# esp32s3_del_v1.net
KiCad netlist of a schematic drawn in EasyEDA Pro
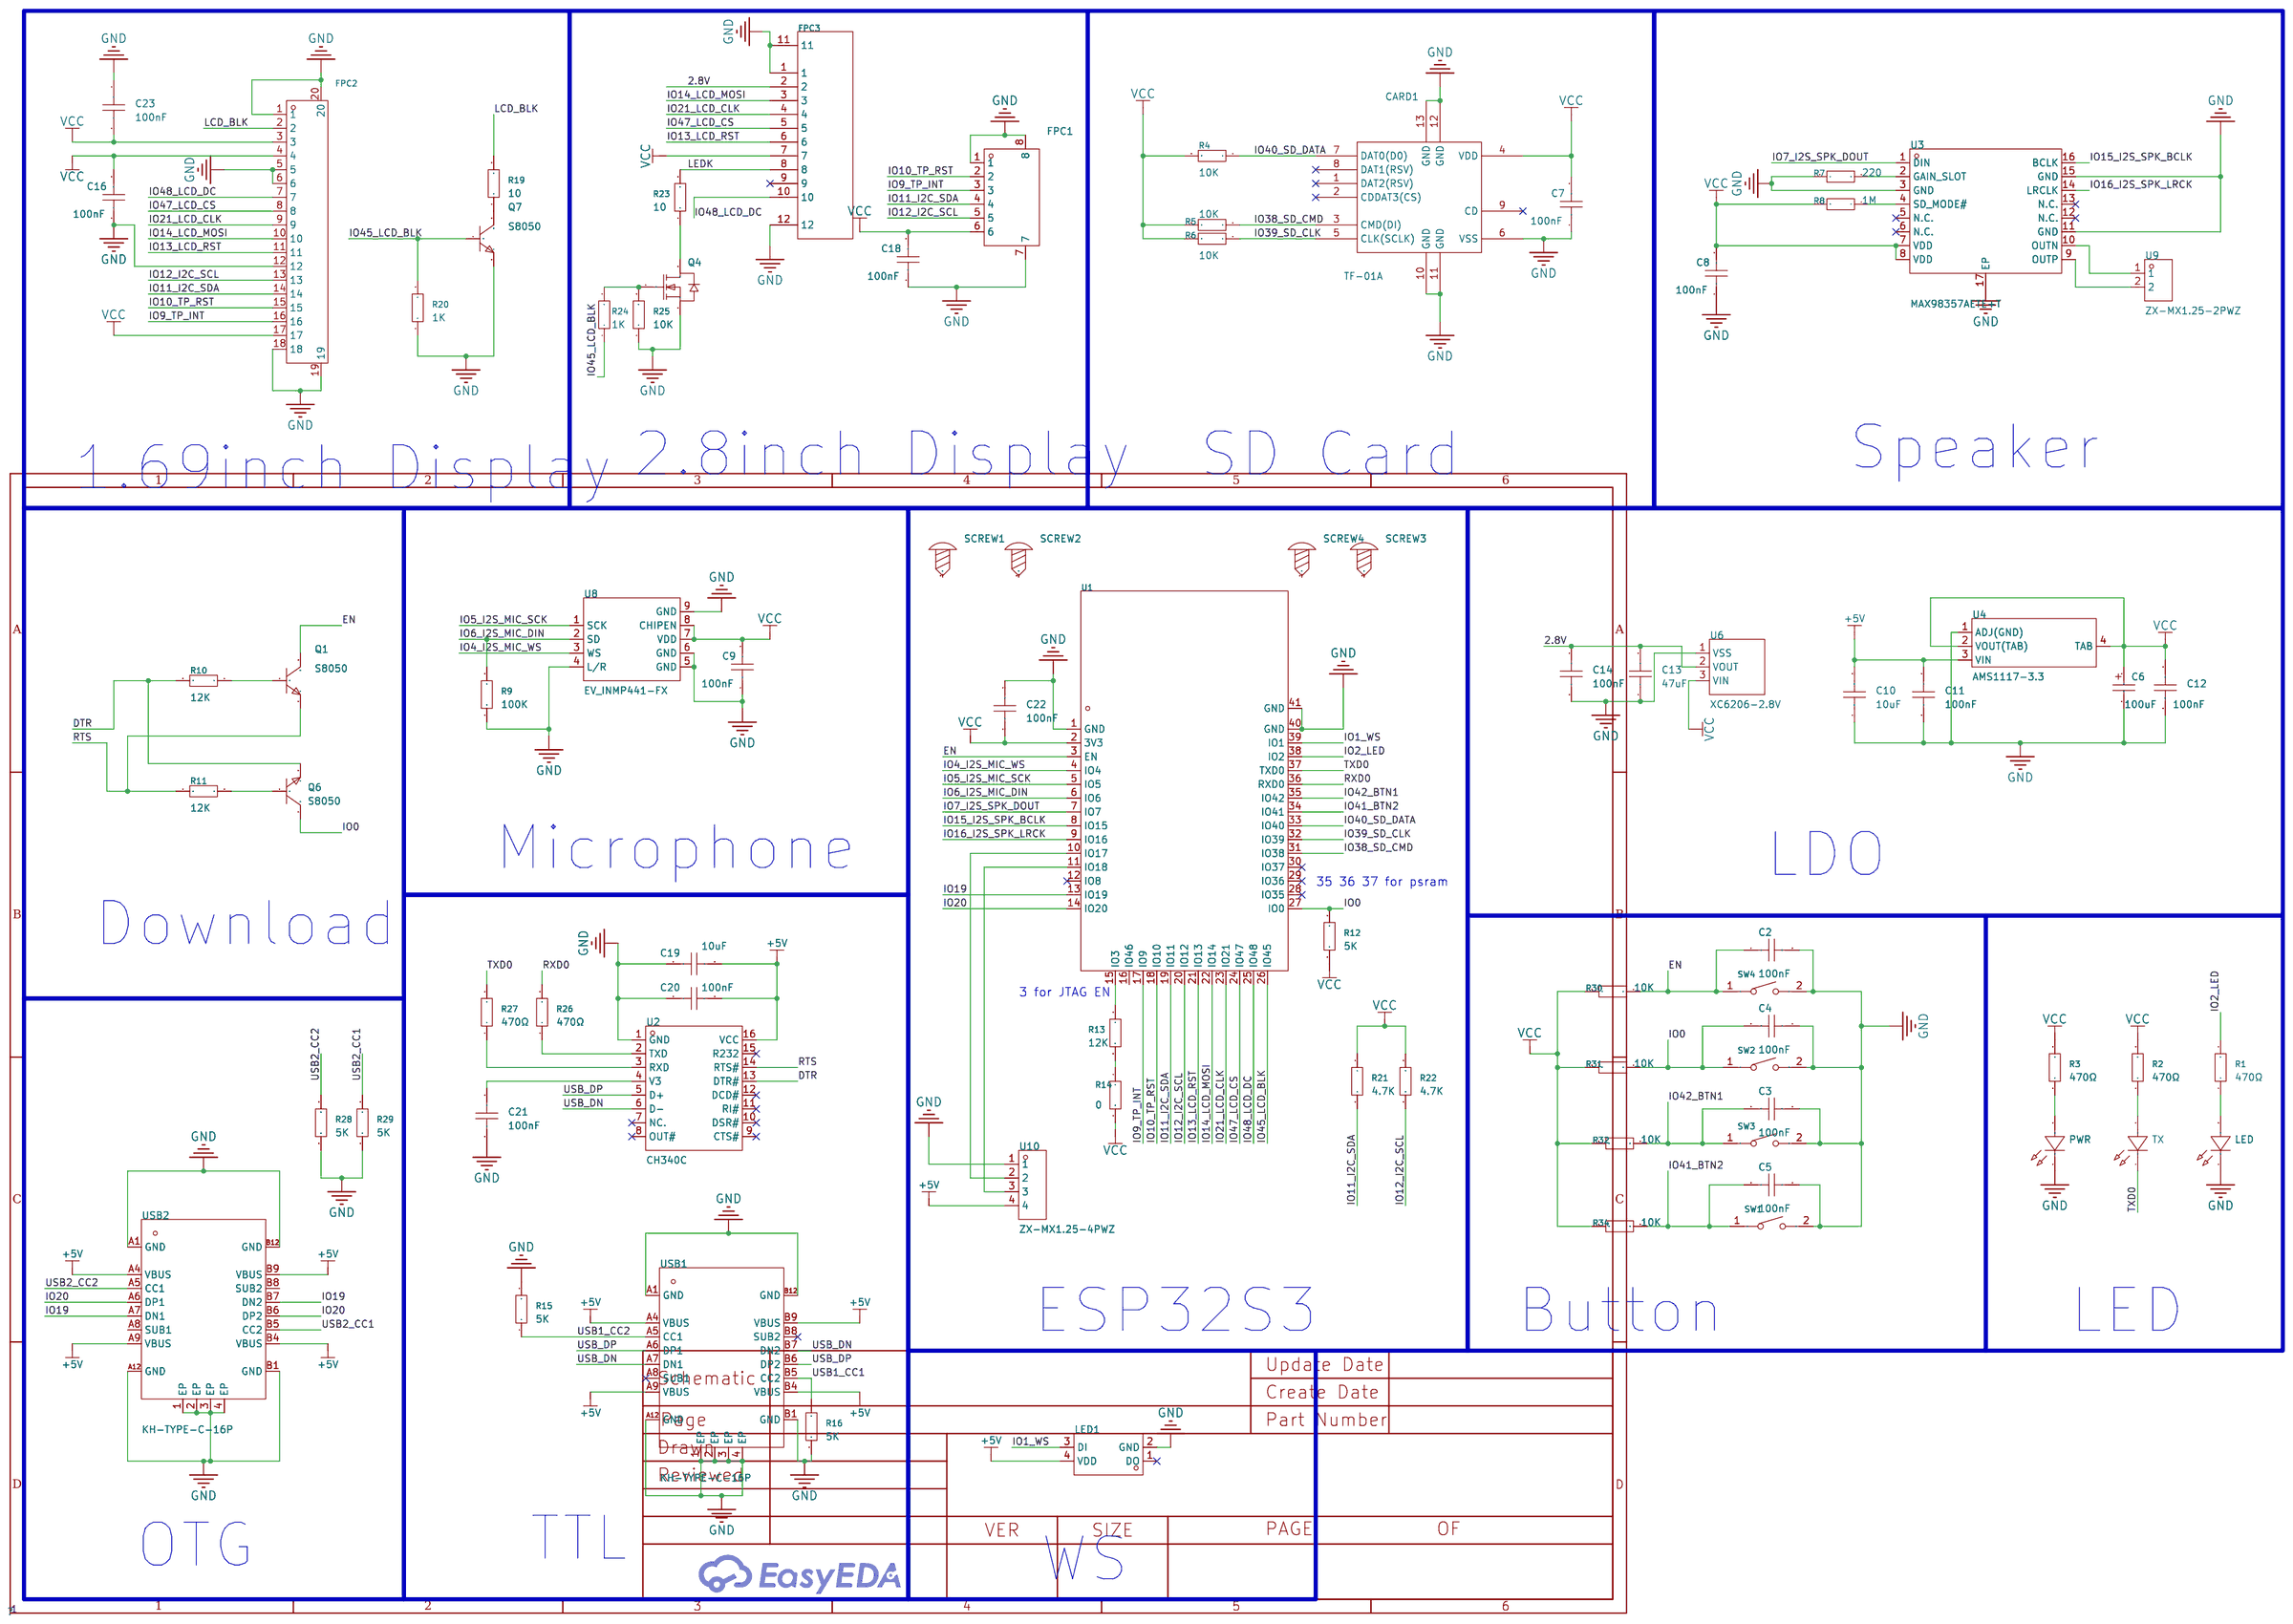
[diagram p0: schematic sheet]

(export (version "E")
  (design (tool "Eeschema 10.0.6"))
  (components
    (comp (ref "C2")
      (value "100nF")
      (footprint "easyedapro:C0402")
      (fields
        (field (name "Manufacturer Part") "CL05B104KO5NNNC")
        (field (name "Manufacturer") "SAMSUNG(三星)")
      )
      (libsource (lib "easyedapro") (part "CL05B104KO5NNNC"))
    )
    (comp (ref "C3")
      (value "100nF")
      (footprint "easyedapro:C0402")
      (fields
        (field (name "Manufacturer Part") "CL05B104KO5NNNC")
        (field (name "Manufacturer") "SAMSUNG(三星)")
      )
      (libsource (lib "easyedapro") (part "CL05B104KO5NNNC"))
    )
    (comp (ref "C4")
      (value "100nF")
      (footprint "easyedapro:C0402")
      (fields
        (field (name "Manufacturer Part") "CL05B104KO5NNNC")
        (field (name "Manufacturer") "SAMSUNG(三星)")
      )
      (libsource (lib "easyedapro") (part "CL05B104KO5NNNC"))
    )
    (comp (ref "C5")
      (value "100nF")
      (footprint "easyedapro:C0402")
      (fields
        (field (name "Manufacturer Part") "CL05B104KO5NNNC")
        (field (name "Manufacturer") "SAMSUNG(三星)")
      )
      (libsource (lib "easyedapro") (part "CL05B104KO5NNNC"))
    )
    (comp (ref "C6")
      (value "100uF")
      (footprint "easyedapro:CASE-B_3528")
      (fields (field (name "Manufacturer Part") "TAJB107K006RNJ") (field (name "Manufacturer") "Kyocera AVX"))
      (libsource (lib "easyedapro") (part "TAJB107K006RNJ"))
    )
    (comp (ref "C7")
      (value "100nF")
      (footprint "easyedapro:C0402")
      (fields
        (field (name "Manufacturer Part") "CL05B104KO5NNNC")
        (field (name "Manufacturer") "SAMSUNG(三星)")
      )
      (libsource (lib "easyedapro") (part "CL05B104KO5NNNC"))
    )
    (comp (ref "C8")
      (value "100nF")
      (footprint "easyedapro:C0402")
      (fields
        (field (name "Manufacturer Part") "CL05B104KO5NNNC")
        (field (name "Manufacturer") "SAMSUNG(三星)")
      )
      (libsource (lib "easyedapro") (part "CL05B104KO5NNNC"))
    )
    (comp (ref "C9")
      (value "100nF")
      (footprint "easyedapro:C0402")
      (fields
        (field (name "Manufacturer Part") "CL05B104KO5NNNC")
        (field (name "Manufacturer") "SAMSUNG(三星)")
      )
      (libsource (lib "easyedapro") (part "CL05B104KO5NNNC"))
    )
    (comp (ref "C10")
      (value "10uF")
      (footprint "easyedapro:C0603")
      (description "Capacitance:10uF Tolerance:±10% Tolerance:±10% Voltage Rating:10V Temperature Coefficient:X5R")
      (fields
        (field (name "Manufacturer Part") "CGA0603X5R106K100JT")
        (field (name "Manufacturer") "HRE(芯声)")
      )
      (libsource (lib "easyedapro") (part "CGA0603X5R106K100JT"))
    )
    (comp (ref "C11")
      (value "100nF")
      (footprint "easyedapro:C0402")
      (fields
        (field (name "Manufacturer Part") "CL05B104KO5NNNC")
        (field (name "Manufacturer") "SAMSUNG(三星)")
      )
      (libsource (lib "easyedapro") (part "CL05B104KO5NNNC"))
    )
    (comp (ref "C12")
      (value "100nF")
      (footprint "easyedapro:C0402")
      (fields
        (field (name "Manufacturer Part") "CL05B104KO5NNNC")
        (field (name "Manufacturer") "SAMSUNG(三星)")
      )
      (libsource (lib "easyedapro") (part "CL05B104KO5NNNC"))
    )
    (comp (ref "C13")
      (value "47uF")
      (footprint "easyedapro:C0603")
      (description "Capacitance:10uF Tolerance:±10% Tolerance:±10% Voltage Rating:10V Temperature Coefficient:X5R")
      (fields
        (field (name "Manufacturer Part") "CGA0603X5R106K100JT")
        (field (name "Manufacturer") "HRE(芯声)")
      )
      (libsource (lib "easyedapro") (part "CGA0603X5R106K100JT"))
    )
    (comp (ref "C14")
      (value "100nF")
      (footprint "easyedapro:C0402")
      (fields
        (field (name "Manufacturer Part") "CL05B104KO5NNNC")
        (field (name "Manufacturer") "SAMSUNG(三星)")
      )
      (libsource (lib "easyedapro") (part "CL05B104KO5NNNC"))
    )
    (comp (ref "C16")
      (value "100nF")
      (footprint "easyedapro:C0402")
      (fields
        (field (name "Manufacturer Part") "CL05B104KO5NNNC")
        (field (name "Manufacturer") "SAMSUNG(三星)")
      )
      (libsource (lib "easyedapro") (part "CL05B104KO5NNNC"))
    )
    (comp (ref "C18")
      (value "100nF")
      (footprint "easyedapro:C0402")
      (fields
        (field (name "Manufacturer Part") "CL05B104KO5NNNC")
        (field (name "Manufacturer") "SAMSUNG(三星)")
      )
      (libsource (lib "easyedapro") (part "CL05B104KO5NNNC"))
    )
    (comp (ref "C19")
      (value "10uF")
      (footprint "easyedapro:C0603")
      (description "Capacitance:10uF Tolerance:±10% Tolerance:±10% Voltage Rating:10V Temperature Coefficient:X5R")
      (fields
        (field (name "Manufacturer Part") "CGA0603X5R106K100JT")
        (field (name "Manufacturer") "HRE(芯声)")
      )
      (libsource (lib "easyedapro") (part "CGA0603X5R106K100JT"))
    )
    (comp (ref "C20")
      (value "100nF")
      (footprint "easyedapro:C0402")
      (fields
        (field (name "Manufacturer Part") "CL05B104KO5NNNC")
        (field (name "Manufacturer") "SAMSUNG(三星)")
      )
      (libsource (lib "easyedapro") (part "CL05B104KO5NNNC"))
    )
    (comp (ref "C21")
      (value "100nF")
      (footprint "easyedapro:C0402")
      (fields
        (field (name "Manufacturer Part") "CL05B104KO5NNNC")
        (field (name "Manufacturer") "SAMSUNG(三星)")
      )
      (libsource (lib "easyedapro") (part "CL05B104KO5NNNC"))
    )
    (comp (ref "C22")
      (value "100nF")
      (footprint "easyedapro:C0402")
      (fields
        (field (name "Manufacturer Part") "CL05B104KO5NNNC")
        (field (name "Manufacturer") "SAMSUNG(三星)")
      )
      (libsource (lib "easyedapro") (part "CL05B104KO5NNNC"))
    )
    (comp (ref "C23")
      (value "100nF")
      (footprint "easyedapro:C0402")
      (fields
        (field (name "Manufacturer Part") "CL05B104KO5NNNC")
        (field (name "Manufacturer") "SAMSUNG(三星)")
      )
      (libsource (lib "easyedapro") (part "CL05B104KO5NNNC"))
    )
    (comp (ref "CARD1")
      (value "TF-01A")
      (footprint "easyedapro:TF-SMD_TF-01A")
      (fields (field (name "Manufacturer") "韩国韩荣"))
      (libsource (lib "easyedapro") (part "TF-01A"))
    )
    (comp (ref "FPC1")
      (value "0.5K-DX-6PWBG")
      (footprint "easyedapro:FPC-SMD_6P-P0.50_DEALON_0.5K-DX-6PWB")
      (fields (field (name "Manufacturer") "HDGC(华德共创)"))
      (libsource (lib "easyedapro") (part "0.5K-DX-6PWBG"))
    )
    (comp (ref "FPC2")
      (value "FPC-05F-18PH20")
      (footprint "easyedapro:FPC-SMD_18P-P0.50_FPC-05F-18PH20")
      (fields (field (name "Manufacturer") "XUNPU(讯普)"))
      (libsource (lib "easyedapro") (part "FPC-05F-18PH20"))
    )
    (comp (ref "FPC3")
      (value "AFC07-S10ECA-00")
      (footprint "easyedapro:FPC-SMD_P0.50-10P_LCS-SJ-H2.0")
      (fields (field (name "Manufacturer") "JS(钜硕电子)"))
      (libsource (lib "easyedapro") (part "AFC07-S10ECA-00"))
    )
    (comp (ref "LED")
      (value "XL-1608SURC-06")
      (footprint "easyedapro:LED0603-RD_RED")
      (fields (field (name "Manufacturer") "XINGLIGHT(成兴光)"))
      (libsource (lib "easyedapro") (part "XL-1608SURC-06"))
    )
    (comp (ref "LED1")
      (value "XL-2020RGBC-WS2812B")
      (footprint "easyedapro:LED-SMD_4P-L2.0-W2.0-BR-1")
      (fields (field (name "Manufacturer") "XINGLIGHT(成兴光)"))
      (libsource (lib "easyedapro") (part "XL-2020RGBC-WS2812B"))
    )
    (comp (ref "PWR")
      (value "XL-1608SURC-06")
      (footprint "easyedapro:LED0603-RD_RED")
      (fields (field (name "Manufacturer") "XINGLIGHT(成兴光)"))
      (libsource (lib "easyedapro") (part "XL-1608SURC-06"))
    )
    (comp (ref "Q1")
      (value "S8050")
      (footprint "easyedapro:SOT-23-3_L2.9-W1.3-P1.90-LS2.3-BR")
      (fields (field (name "Manufacturer") "宏嘉诚"))
      (libsource (lib "easyedapro") (part "S8050_C20069125"))
    )
    (comp (ref "Q4")
      (value "Si2302CDS-T1-GE3")
      (footprint "easyedapro:SOT-23_L2.9-W1.3-P1.90-LS2.4-BR")
      (fields (field (name "Manufacturer") "VISHAY(威世)"))
      (libsource (lib "easyedapro") (part "Si2302CDS-T1-GE3"))
    )
    (comp (ref "Q6")
      (value "S8050")
      (footprint "easyedapro:SOT-23-3_L2.9-W1.3-P1.90-LS2.3-BR")
      (fields (field (name "Manufacturer") "宏嘉诚"))
      (libsource (lib "easyedapro") (part "S8050_C20069125"))
    )
    (comp (ref "Q7")
      (value "S8050")
      (footprint "easyedapro:SOT-23-3_L2.9-W1.3-P1.90-LS2.3-BR")
      (fields (field (name "Manufacturer") "宏嘉诚"))
      (libsource (lib "easyedapro") (part "S8050_C20069125"))
    )
    (comp (ref "R1")
      (value "470Ω")
      (footprint "easyedapro:R0402")
      (fields
        (field (name "Manufacturer Part") "0402WGF4700TCE")
        (field (name "Manufacturer") "UNI-ROYAL(厚声)")
      )
      (libsource (lib "easyedapro") (part "0402WGF4700TCE"))
    )
    (comp (ref "R2")
      (value "470Ω")
      (footprint "easyedapro:R0402")
      (fields
        (field (name "Manufacturer Part") "0402WGF4700TCE")
        (field (name "Manufacturer") "UNI-ROYAL(厚声)")
      )
      (libsource (lib "easyedapro") (part "0402WGF4700TCE"))
    )
    (comp (ref "R3")
      (value "470Ω")
      (footprint "easyedapro:R0402")
      (fields
        (field (name "Manufacturer Part") "0402WGF4700TCE")
        (field (name "Manufacturer") "UNI-ROYAL(厚声)")
      )
      (libsource (lib "easyedapro") (part "0402WGF4700TCE"))
    )
    (comp (ref "R4")
      (value "10K")
      (footprint "easyedapro:R0402")
      (fields
        (field (name "Manufacturer Part") "0402WGF4700TCE")
        (field (name "Manufacturer") "UNI-ROYAL(厚声)")
      )
      (libsource (lib "easyedapro") (part "0402WGF4700TCE"))
    )
    (comp (ref "R5")
      (value "10K")
      (footprint "easyedapro:R0402")
      (fields
        (field (name "Manufacturer Part") "0402WGF4700TCE")
        (field (name "Manufacturer") "UNI-ROYAL(厚声)")
      )
      (libsource (lib "easyedapro") (part "0402WGF4700TCE"))
    )
    (comp (ref "R6")
      (value "10K")
      (footprint "easyedapro:R0402")
      (fields
        (field (name "Manufacturer Part") "0402WGF4700TCE")
        (field (name "Manufacturer") "UNI-ROYAL(厚声)")
      )
      (libsource (lib "easyedapro") (part "0402WGF4700TCE"))
    )
    (comp (ref "R7")
      (value "220")
      (footprint "easyedapro:R0402")
      (fields
        (field (name "Manufacturer Part") "0402WGF4700TCE")
        (field (name "Manufacturer") "UNI-ROYAL(厚声)")
      )
      (libsource (lib "easyedapro") (part "0402WGF4700TCE"))
    )
    (comp (ref "R8")
      (value "1M")
      (footprint "easyedapro:R0402")
      (fields
        (field (name "Manufacturer Part") "0402WGF4700TCE")
        (field (name "Manufacturer") "UNI-ROYAL(厚声)")
      )
      (libsource (lib "easyedapro") (part "0402WGF4700TCE"))
    )
    (comp (ref "R9")
      (value "100K")
      (footprint "easyedapro:R0402")
      (fields
        (field (name "Manufacturer Part") "0402WGF4700TCE")
        (field (name "Manufacturer") "UNI-ROYAL(厚声)")
      )
      (libsource (lib "easyedapro") (part "0402WGF4700TCE"))
    )
    (comp (ref "R10")
      (value "12K")
      (footprint "easyedapro:R0402")
      (fields
        (field (name "Manufacturer Part") "0402WGF4700TCE")
        (field (name "Manufacturer") "UNI-ROYAL(厚声)")
      )
      (libsource (lib "easyedapro") (part "0402WGF4700TCE"))
    )
    (comp (ref "R11")
      (value "12K")
      (footprint "easyedapro:R0402")
      (fields
        (field (name "Manufacturer Part") "0402WGF4700TCE")
        (field (name "Manufacturer") "UNI-ROYAL(厚声)")
      )
      (libsource (lib "easyedapro") (part "0402WGF4700TCE"))
    )
    (comp (ref "R12")
      (value "5K")
      (footprint "easyedapro:R0402")
      (fields
        (field (name "Manufacturer Part") "0402WGF4700TCE")
        (field (name "Manufacturer") "UNI-ROYAL(厚声)")
      )
      (libsource (lib "easyedapro") (part "0402WGF4700TCE"))
    )
    (comp (ref "R13")
      (value "12K")
      (footprint "easyedapro:R0402")
      (fields
        (field (name "Manufacturer Part") "0402WGF4700TCE")
        (field (name "Manufacturer") "UNI-ROYAL(厚声)")
      )
      (libsource (lib "easyedapro") (part "0402WGF4700TCE"))
    )
    (comp (ref "R14")
      (value "0")
      (footprint "easyedapro:R0402")
      (fields
        (field (name "Manufacturer Part") "0402WGF4700TCE")
        (field (name "Manufacturer") "UNI-ROYAL(厚声)")
      )
      (libsource (lib "easyedapro") (part "0402WGF4700TCE"))
    )
    (comp (ref "R15")
      (value "5K")
      (footprint "easyedapro:R0402")
      (fields
        (field (name "Manufacturer Part") "0402WGF4700TCE")
        (field (name "Manufacturer") "UNI-ROYAL(厚声)")
      )
      (libsource (lib "easyedapro") (part "0402WGF4700TCE"))
    )
    (comp (ref "R16")
      (value "5K")
      (footprint "easyedapro:R0402")
      (fields
        (field (name "Manufacturer Part") "0402WGF4700TCE")
        (field (name "Manufacturer") "UNI-ROYAL(厚声)")
      )
      (libsource (lib "easyedapro") (part "0402WGF4700TCE"))
    )
    (comp (ref "R19")
      (value "10")
      (footprint "easyedapro:R0402")
      (fields
        (field (name "Manufacturer Part") "0402WGF4700TCE")
        (field (name "Manufacturer") "UNI-ROYAL(厚声)")
      )
      (libsource (lib "easyedapro") (part "0402WGF4700TCE"))
    )
    (comp (ref "R20")
      (value "1K")
      (footprint "easyedapro:R0402")
      (fields
        (field (name "Manufacturer Part") "0402WGF4700TCE")
        (field (name "Manufacturer") "UNI-ROYAL(厚声)")
      )
      (libsource (lib "easyedapro") (part "0402WGF4700TCE"))
    )
    (comp (ref "R21")
      (value "4.7K")
      (footprint "easyedapro:R0402")
      (fields
        (field (name "Manufacturer Part") "0402WGF4700TCE")
        (field (name "Manufacturer") "UNI-ROYAL(厚声)")
      )
      (libsource (lib "easyedapro") (part "0402WGF4700TCE"))
    )
    (comp (ref "R22")
      (value "4.7K")
      (footprint "easyedapro:R0402")
      (fields
        (field (name "Manufacturer Part") "0402WGF4700TCE")
        (field (name "Manufacturer") "UNI-ROYAL(厚声)")
      )
      (libsource (lib "easyedapro") (part "0402WGF4700TCE"))
    )
    (comp (ref "R23")
      (value "10")
      (footprint "easyedapro:R0402")
      (fields
        (field (name "Manufacturer Part") "0402WGF4700TCE")
        (field (name "Manufacturer") "UNI-ROYAL(厚声)")
      )
      (libsource (lib "easyedapro") (part "0402WGF4700TCE"))
    )
    (comp (ref "R24")
      (value "1K")
      (footprint "easyedapro:R0402")
      (fields
        (field (name "Manufacturer Part") "0402WGF4700TCE")
        (field (name "Manufacturer") "UNI-ROYAL(厚声)")
      )
      (libsource (lib "easyedapro") (part "0402WGF4700TCE"))
    )
    (comp (ref "R25")
      (value "10K")
      (footprint "easyedapro:R0402")
      (fields
        (field (name "Manufacturer Part") "0402WGF4700TCE")
        (field (name "Manufacturer") "UNI-ROYAL(厚声)")
      )
      (libsource (lib "easyedapro") (part "0402WGF4700TCE"))
    )
    (comp (ref "R26")
      (value "470Ω")
      (footprint "easyedapro:R0402")
      (fields
        (field (name "Manufacturer Part") "0402WGF4700TCE")
        (field (name "Manufacturer") "UNI-ROYAL(厚声)")
      )
      (libsource (lib "easyedapro") (part "0402WGF4700TCE"))
    )
    (comp (ref "R27")
      (value "470Ω")
      (footprint "easyedapro:R0402")
      (fields
        (field (name "Manufacturer Part") "0402WGF4700TCE")
        (field (name "Manufacturer") "UNI-ROYAL(厚声)")
      )
      (libsource (lib "easyedapro") (part "0402WGF4700TCE"))
    )
    (comp (ref "R28")
      (value "5K")
      (footprint "easyedapro:R0402")
      (fields
        (field (name "Manufacturer Part") "0402WGF4700TCE")
        (field (name "Manufacturer") "UNI-ROYAL(厚声)")
      )
      (libsource (lib "easyedapro") (part "0402WGF4700TCE"))
    )
    (comp (ref "R29")
      (value "5K")
      (footprint "easyedapro:R0402")
      (fields
        (field (name "Manufacturer Part") "0402WGF4700TCE")
        (field (name "Manufacturer") "UNI-ROYAL(厚声)")
      )
      (libsource (lib "easyedapro") (part "0402WGF4700TCE"))
    )
    (comp (ref "R30")
      (value "10K")
      (footprint "easyedapro:R0402")
      (fields
        (field (name "Manufacturer Part") "0402WGF4700TCE")
        (field (name "Manufacturer") "UNI-ROYAL(厚声)")
      )
      (libsource (lib "easyedapro") (part "0402WGF4700TCE"))
    )
    (comp (ref "R31")
      (value "10K")
      (footprint "easyedapro:R0402")
      (fields
        (field (name "Manufacturer Part") "0402WGF4700TCE")
        (field (name "Manufacturer") "UNI-ROYAL(厚声)")
      )
      (libsource (lib "easyedapro") (part "0402WGF4700TCE"))
    )
    (comp (ref "R32")
      (value "10K")
      (footprint "easyedapro:R0402")
      (fields
        (field (name "Manufacturer Part") "0402WGF4700TCE")
        (field (name "Manufacturer") "UNI-ROYAL(厚声)")
      )
      (libsource (lib "easyedapro") (part "0402WGF4700TCE"))
    )
    (comp (ref "R34")
      (value "10K")
      (footprint "easyedapro:R0402")
      (fields
        (field (name "Manufacturer Part") "0402WGF4700TCE")
        (field (name "Manufacturer") "UNI-ROYAL(厚声)")
      )
      (libsource (lib "easyedapro") (part "0402WGF4700TCE"))
    )
    (comp (ref "SCREW1")
      (value "~")
      (footprint "easyedapro:Screw-Hole-M2")
      (libsource (lib "easyedapro") (part "Screw-Hole"))
    )
    (comp (ref "SCREW2")
      (value "~")
      (footprint "easyedapro:Screw-Hole-M2")
      (libsource (lib "easyedapro") (part "Screw-Hole"))
    )
    (comp (ref "SCREW3")
      (value "~")
      (footprint "easyedapro:Screw-Hole-M2")
      (libsource (lib "easyedapro") (part "Screw-Hole"))
    )
    (comp (ref "SCREW4")
      (value "~")
      (footprint "easyedapro:Screw-Hole-M2")
      (libsource (lib "easyedapro") (part "Screw-Hole"))
    )
    (comp (ref "SW1")
      (value "TS-1088-AR02016")
      (footprint "easyedapro:SW-SMD_L3.9-W3.0-P4.45")
      (fields (field (name "Manufacturer") "XUNPU(讯普)"))
      (libsource (lib "easyedapro") (part "TS-1088-AR02016"))
    )
    (comp (ref "SW2")
      (value "TS-1088-AR02016")
      (footprint "easyedapro:SW-SMD_L3.9-W3.0-P4.45")
      (fields (field (name "Manufacturer") "XUNPU(讯普)"))
      (libsource (lib "easyedapro") (part "TS-1088-AR02016"))
    )
    (comp (ref "SW3")
      (value "TS-1088-AR02016")
      (footprint "easyedapro:SW-SMD_L3.9-W3.0-P4.45")
      (fields (field (name "Manufacturer") "XUNPU(讯普)"))
      (libsource (lib "easyedapro") (part "TS-1088-AR02016"))
    )
    (comp (ref "SW4")
      (value "TS-1088-AR02016")
      (footprint "easyedapro:SW-SMD_L3.9-W3.0-P4.45")
      (fields (field (name "Manufacturer") "XUNPU(讯普)"))
      (libsource (lib "easyedapro") (part "TS-1088-AR02016"))
    )
    (comp (ref "TX")
      (value "XL-1608SURC-06")
      (footprint "easyedapro:LED0603-RD_RED")
      (fields (field (name "Manufacturer") "XINGLIGHT(成兴光)"))
      (libsource (lib "easyedapro") (part "XL-1608SURC-06"))
    )
    (comp (ref "U1")
      (value "ESP32-S3-WROOM-1-N16R8")
      (footprint "easyedapro:WIRELM-SMD_ESP32-S3-WROOM-1")
      (fields (field (name "Manufacturer") "ESPRESSIF(乐鑫)"))
      (libsource (lib "easyedapro") (part "ESP32-S3-WROOM-1(N16R8)"))
    )
    (comp (ref "U2")
      (value "CH340C")
      (footprint "easyedapro:SOP-16_L10.0-W3.9-P1.27-LS6.0-BL")
      (fields (field (name "Manufacturer") "WCH(南京沁恒)"))
      (libsource (lib "easyedapro") (part "CH340C"))
    )
    (comp (ref "U3")
      (value "MAX98357AETE+T")
      (footprint "easyedapro:TQFN-16_L3.0-W3.0-P0.50-BL-EP1.5")
      (fields (field (name "Manufacturer") "ADI(亚德诺)/MAXIM(美信)"))
      (libsource (lib "easyedapro") (part "MAX98357AETE+T"))
    )
    (comp (ref "U4")
      (value "AMS1117-3.3")
      (footprint "easyedapro:SOT-223-4_L6.5-W3.5-P2.30-LS7.0-BR")
      (fields (field (name "Manufacturer") "UMW(友台半导体)"))
      (libsource (lib "easyedapro") (part "AMS1117-3.3_C347222"))
    )
    (comp (ref "U6")
      (value "XC6206-2.8V")
      (footprint "easyedapro:SOT-23-3_L2.9-W1.6-P1.90-LS2.8-BR")
      (fields (field (name "Manufacturer") "YONGYUTAI(永裕泰)"))
      (libsource (lib "easyedapro") (part "XC6206-2.8V"))
    )
    (comp (ref "U8")
      (value "EV_INMP441-FX")
      (footprint "easyedapro:MID-SMD_L4.7-W3.8_INMP441ACEZ")
      (description "Sensor Type:Audio")
      (fields (field (name "Manufacturer") "TDK InvenSense(应美盛)"))
      (libsource (lib "easyedapro") (part "EV_INMP441-FX"))
    )
    (comp (ref "U9")
      (value "ZX-MX1.25-2PWZ")
      (footprint "easyedapro:CONN-TH_2P-P1.25_ZX-MX1.25-2PWZ")
      (fields (field (name "Manufacturer") "Megastar(兆星)"))
      (libsource (lib "easyedapro") (part "ZX-MX1.25-2PWZ"))
    )
    (comp (ref "U10")
      (value "ZX-MX1.25-4PWZ")
      (footprint "easyedapro:CONN-TH_4P-P1.25_ZX-MX1.25-4PWZ")
      (fields (field (name "Manufacturer") "Megastar(兆星)"))
      (libsource (lib "easyedapro") (part "ZX-MX1.25-4PWZ"))
    )
    (comp (ref "USB1")
      (value "KH-TYPE-C-16P")
      (footprint "easyedapro:USB-C-SMD_KH-TYPE-C-16P")
      (fields (field (name "Manufacturer") "kinghelm(金航标)"))
      (libsource (lib "easyedapro") (part "KH-TYPE-C-16P"))
    )
    (comp (ref "USB2")
      (value "KH-TYPE-C-16P")
      (footprint "easyedapro:USB-C-SMD_KH-TYPE-C-16P")
      (fields (field (name "Manufacturer") "kinghelm(金航标)"))
      (libsource (lib "easyedapro") (part "KH-TYPE-C-16P"))
    )
  )
  (nets
    (net (code "1") (name "+5V") (class "Default")
      (node (ref "C10") (pin "2") (pinfunction "2_2") (pintype "unspecified"))
      (node (ref "C11") (pin "1") (pinfunction "1_1") (pintype "unspecified"))
      (node (ref "C19") (pin "1") (pinfunction "1_1") (pintype "unspecified"))
      (node (ref "C20") (pin "2") (pinfunction "2_2") (pintype "unspecified"))
      (node (ref "LED1") (pin "4") (pinfunction "VDD_4") (pintype "unspecified"))
      (node (ref "U10") (pin "4") (pinfunction "4_4") (pintype "unspecified"))
      (node (ref "U2") (pin "16") (pinfunction "VCC_16") (pintype "unspecified"))
      (node (ref "U4") (pin "3") (pinfunction "VIN_3") (pintype "unspecified"))
      (node (ref "USB1") (pin "A4") (pinfunction "VBUS_A4") (pintype "unspecified"))
      (node (ref "USB1") (pin "A9") (pinfunction "VBUS_A9") (pintype "unspecified"))
      (node (ref "USB1") (pin "B4") (pinfunction "VBUS_B4") (pintype "unspecified"))
      (node (ref "USB1") (pin "B9") (pinfunction "VBUS_B9") (pintype "unspecified"))
      (node (ref "USB2") (pin "A4") (pinfunction "VBUS_A4") (pintype "unspecified"))
      (node (ref "USB2") (pin "A9") (pinfunction "VBUS_A9") (pintype "unspecified"))
      (node (ref "USB2") (pin "B4") (pinfunction "VBUS_B4") (pintype "unspecified"))
      (node (ref "USB2") (pin "B9") (pinfunction "VBUS_B9") (pintype "unspecified"))
    )
    (net (code "2") (name "/2.8V") (class "Default")
      (node (ref "C13") (pin "2") (pinfunction "2_2") (pintype "unspecified"))
      (node (ref "C14") (pin "1") (pinfunction "1_1") (pintype "unspecified"))
      (node (ref "FPC3") (pin "2") (pinfunction "2_2") (pintype "input"))
      (node (ref "U6") (pin "2") (pinfunction "VOUT_2") (pintype "unspecified"))
    )
    (net (code "3") (name "/DTR") (class "Default")
      (node (ref "Q6") (pin "2") (pinfunction "E_2") (pintype "input"))
      (node (ref "R10") (pin "2") (pinfunction "2_2") (pintype "input"))
      (node (ref "U2") (pin "13") (pinfunction "DTR#_13") (pintype "unspecified"))
    )
    (net (code "4") (name "/EN") (class "Default")
      (node (ref "C2") (pin "1") (pinfunction "1_1") (pintype "unspecified"))
      (node (ref "Q1") (pin "3") (pinfunction "C_3") (pintype "input"))
      (node (ref "R30") (pin "1") (pinfunction "1_1") (pintype "input"))
      (node (ref "SW4") (pin "1") (pinfunction "1_1") (pintype "input"))
      (node (ref "U1") (pin "3") (pinfunction "EN_3") (pintype "input"))
    )
    (net (code "5") (name "/IO0") (class "Default")
      (node (ref "C4") (pin "2") (pinfunction "2_2") (pintype "unspecified"))
      (node (ref "Q6") (pin "3") (pinfunction "C_3") (pintype "input"))
      (node (ref "R12") (pin "1") (pinfunction "1_1") (pintype "input"))
      (node (ref "R31") (pin "1") (pinfunction "1_1") (pintype "input"))
      (node (ref "SW2") (pin "1") (pinfunction "1_1") (pintype "input"))
      (node (ref "U1") (pin "27") (pinfunction "IO0_27") (pintype "input"))
    )
    (net (code "6") (name "/IO1_WS") (class "Default")
      (node (ref "LED1") (pin "3") (pinfunction "DI_3") (pintype "unspecified"))
      (node (ref "U1") (pin "39") (pinfunction "IO1_39") (pintype "input"))
    )
    (net (code "7") (name "/IO2_LED") (class "Default")
      (node (ref "R1") (pin "2") (pinfunction "2_2") (pintype "input"))
      (node (ref "U1") (pin "38") (pinfunction "IO2_38") (pintype "input"))
    )
    (net (code "8") (name "/IO4_I2S_MIC_WS") (class "Default")
      (node (ref "U1") (pin "4") (pinfunction "IO4_4") (pintype "input"))
      (node (ref "U8") (pin "3") (pinfunction "WS_3") (pintype "unspecified"))
    )
    (net (code "9") (name "/IO5_I2S_MIC_SCK") (class "Default")
      (node (ref "U1") (pin "5") (pinfunction "IO5_5") (pintype "input"))
      (node (ref "U8") (pin "1") (pinfunction "SCK_1") (pintype "unspecified"))
    )
    (net (code "10") (name "/IO6_I2S_MIC_DIN") (class "Default")
      (node (ref "R9") (pin "2") (pinfunction "2_2") (pintype "input"))
      (node (ref "U1") (pin "6") (pinfunction "IO6_6") (pintype "input"))
      (node (ref "U8") (pin "2") (pinfunction "SD_2") (pintype "unspecified"))
    )
    (net (code "11") (name "/IO7_I2S_SPK_DOUT") (class "Default")
      (node (ref "U1") (pin "7") (pinfunction "IO7_7") (pintype "input"))
      (node (ref "U3") (pin "1") (pinfunction "DIN_1") (pintype "unspecified"))
    )
    (net (code "12") (name "/IO9_TP_INT") (class "Default")
      (node (ref "FPC1") (pin "3") (pinfunction "3_3") (pintype "unspecified"))
      (node (ref "FPC2") (pin "16") (pinfunction "16_16") (pintype "input"))
      (node (ref "U1") (pin "17") (pinfunction "IO9_17") (pintype "input"))
    )
    (net (code "13") (name "/IO10_TP_RST") (class "Default")
      (node (ref "FPC1") (pin "2") (pinfunction "2_2") (pintype "unspecified"))
      (node (ref "FPC2") (pin "15") (pinfunction "15_15") (pintype "input"))
      (node (ref "U1") (pin "18") (pinfunction "IO10_18") (pintype "input"))
    )
    (net (code "14") (name "/IO11_I2C_SDA") (class "Default")
      (node (ref "FPC1") (pin "4") (pinfunction "4_4") (pintype "unspecified"))
      (node (ref "FPC2") (pin "14") (pinfunction "14_14") (pintype "input"))
      (node (ref "R21") (pin "2") (pinfunction "2_2") (pintype "input"))
      (node (ref "U1") (pin "19") (pinfunction "IO11_19") (pintype "input"))
    )
    (net (code "15") (name "/IO12_I2C_SCL") (class "Default")
      (node (ref "FPC1") (pin "5") (pinfunction "5_5") (pintype "unspecified"))
      (node (ref "FPC2") (pin "13") (pinfunction "13_13") (pintype "input"))
      (node (ref "R22") (pin "2") (pinfunction "2_2") (pintype "input"))
      (node (ref "U1") (pin "20") (pinfunction "IO12_20") (pintype "input"))
    )
    (net (code "16") (name "/IO13_LCD_RST") (class "Default")
      (node (ref "FPC2") (pin "11") (pinfunction "11_11") (pintype "input"))
      (node (ref "FPC3") (pin "6") (pinfunction "6_6") (pintype "input"))
      (node (ref "U1") (pin "21") (pinfunction "IO13_21") (pintype "input"))
    )
    (net (code "17") (name "/IO14_LCD_MOSI") (class "Default")
      (node (ref "FPC2") (pin "10") (pinfunction "10_10") (pintype "input"))
      (node (ref "FPC3") (pin "3") (pinfunction "3_3") (pintype "input"))
      (node (ref "U1") (pin "22") (pinfunction "IO14_22") (pintype "input"))
    )
    (net (code "18") (name "/IO15_I2S_SPK_BCLK") (class "Default")
      (node (ref "U1") (pin "8") (pinfunction "IO15_8") (pintype "input"))
      (node (ref "U3") (pin "16") (pinfunction "BCLK_16") (pintype "unspecified"))
    )
    (net (code "19") (name "/IO16_I2S_SPK_LRCK") (class "Default")
      (node (ref "U1") (pin "9") (pinfunction "IO16_9") (pintype "input"))
      (node (ref "U3") (pin "14") (pinfunction "LRCLK_14") (pintype "unspecified"))
    )
    (net (code "20") (name "/IO19") (class "Default")
      (node (ref "U1") (pin "13") (pinfunction "IO19_13") (pintype "input"))
      (node (ref "USB2") (pin "A7") (pinfunction "DN1_A7") (pintype "unspecified"))
      (node (ref "USB2") (pin "B7") (pinfunction "DN2_B7") (pintype "unspecified"))
    )
    (net (code "21") (name "/IO20") (class "Default")
      (node (ref "U1") (pin "14") (pinfunction "IO20_14") (pintype "input"))
      (node (ref "USB2") (pin "A6") (pinfunction "DP1_A6") (pintype "unspecified"))
      (node (ref "USB2") (pin "B6") (pinfunction "DP2_B6") (pintype "unspecified"))
    )
    (net (code "22") (name "/IO21_LCD_CLK") (class "Default")
      (node (ref "FPC2") (pin "9") (pinfunction "9_9") (pintype "input"))
      (node (ref "FPC3") (pin "4") (pinfunction "4_4") (pintype "input"))
      (node (ref "U1") (pin "23") (pinfunction "IO21_23") (pintype "input"))
    )
    (net (code "23") (name "/IO38_SD_CMD") (class "Default")
      (node (ref "CARD1") (pin "3") (pinfunction "CMD(DI)_3") (pintype "input"))
      (node (ref "R5") (pin "1") (pinfunction "1_1") (pintype "input"))
      (node (ref "U1") (pin "31") (pinfunction "IO38_31") (pintype "input"))
    )
    (net (code "24") (name "/IO39_SD_CLK") (class "Default")
      (node (ref "CARD1") (pin "5") (pinfunction "CLK(SCLK)_5") (pintype "input"))
      (node (ref "R6") (pin "1") (pinfunction "1_1") (pintype "input"))
      (node (ref "U1") (pin "32") (pinfunction "IO39_32") (pintype "input"))
    )
    (net (code "25") (name "/IO40_SD_DATA") (class "Default")
      (node (ref "CARD1") (pin "7") (pinfunction "DAT0(D0)_7") (pintype "bidirectional"))
      (node (ref "R4") (pin "1") (pinfunction "1_1") (pintype "input"))
      (node (ref "U1") (pin "33") (pinfunction "IO40_33") (pintype "input"))
    )
    (net (code "26") (name "/IO41_BTN2") (class "Default")
      (node (ref "C5") (pin "2") (pinfunction "2_2") (pintype "unspecified"))
      (node (ref "R34") (pin "1") (pinfunction "1_1") (pintype "input"))
      (node (ref "SW1") (pin "1") (pinfunction "1_1") (pintype "input"))
      (node (ref "U1") (pin "34") (pinfunction "IO41_34") (pintype "input"))
    )
    (net (code "27") (name "/IO42_BTN1") (class "Default")
      (node (ref "C3") (pin "2") (pinfunction "2_2") (pintype "unspecified"))
      (node (ref "R32") (pin "1") (pinfunction "1_1") (pintype "input"))
      (node (ref "SW3") (pin "1") (pinfunction "1_1") (pintype "input"))
      (node (ref "U1") (pin "35") (pinfunction "IO42_35") (pintype "input"))
    )
    (net (code "28") (name "/IO45_LCD_BLK") (class "Default")
      (node (ref "Q7") (pin "1") (pinfunction "B_1") (pintype "input"))
      (node (ref "R20") (pin "2") (pinfunction "2_2") (pintype "input"))
      (node (ref "R24") (pin "1") (pinfunction "1_1") (pintype "input"))
      (node (ref "U1") (pin "26") (pinfunction "IO45_26") (pintype "input"))
    )
    (net (code "29") (name "/IO47_LCD_CS") (class "Default")
      (node (ref "FPC2") (pin "8") (pinfunction "8_8") (pintype "input"))
      (node (ref "FPC3") (pin "5") (pinfunction "5_5") (pintype "input"))
      (node (ref "U1") (pin "24") (pinfunction "IO47_24") (pintype "input"))
    )
    (net (code "30") (name "/IO48_LCD_DC") (class "Default")
      (node (ref "FPC2") (pin "7") (pinfunction "7_7") (pintype "input"))
      (node (ref "FPC3") (pin "10") (pinfunction "10_10") (pintype "input"))
      (node (ref "U1") (pin "25") (pinfunction "IO48_25") (pintype "input"))
    )
    (net (code "31") (name "/LCD_BLK") (class "Default")
      (node (ref "FPC2") (pin "2") (pinfunction "2_2") (pintype "input"))
      (node (ref "R19") (pin "2") (pinfunction "2_2") (pintype "input"))
    )
    (net (code "32") (name "/LEDK") (class "Default")
      (node (ref "FPC3") (pin "8") (pinfunction "8_8") (pintype "input"))
      (node (ref "R23") (pin "2") (pinfunction "2_2") (pintype "input"))
    )
    (net (code "33") (name "/RTS") (class "Default")
      (node (ref "Q1") (pin "2") (pinfunction "E_2") (pintype "input"))
      (node (ref "R11") (pin "2") (pinfunction "2_2") (pintype "input"))
      (node (ref "U2") (pin "14") (pinfunction "RTS#_14") (pintype "unspecified"))
    )
    (net (code "34") (name "/RXD0") (class "Default")
      (node (ref "R26") (pin "2") (pinfunction "2_2") (pintype "input"))
      (node (ref "U1") (pin "36") (pinfunction "RXD0_36") (pintype "input"))
    )
    (net (code "35") (name "/TXD0") (class "Default")
      (node (ref "R27") (pin "2") (pinfunction "2_2") (pintype "input"))
      (node (ref "TX") (pin "1") (pinfunction "K_1") (pintype "unspecified"))
      (node (ref "U1") (pin "37") (pinfunction "TXD0_37") (pintype "input"))
    )
    (net (code "36") (name "/USB1_CC1") (class "Default")
      (node (ref "R16") (pin "2") (pinfunction "2_2") (pintype "input"))
      (node (ref "USB1") (pin "B5") (pinfunction "CC2_B5") (pintype "unspecified"))
    )
    (net (code "37") (name "/USB1_CC2") (class "Default")
      (node (ref "R15") (pin "1") (pinfunction "1_1") (pintype "input"))
      (node (ref "USB1") (pin "A5") (pinfunction "CC1_A5") (pintype "unspecified"))
    )
    (net (code "38") (name "/USB2_CC1") (class "Default")
      (node (ref "R29") (pin "2") (pinfunction "2_2") (pintype "input"))
      (node (ref "USB2") (pin "B5") (pinfunction "CC2_B5") (pintype "unspecified"))
    )
    (net (code "39") (name "/USB2_CC2") (class "Default")
      (node (ref "R28") (pin "2") (pinfunction "2_2") (pintype "input"))
      (node (ref "USB2") (pin "A5") (pinfunction "CC1_A5") (pintype "unspecified"))
    )
    (net (code "40") (name "/USB_DN") (class "Default")
      (node (ref "U2") (pin "6") (pinfunction "D-_6") (pintype "unspecified"))
      (node (ref "USB1") (pin "A7") (pinfunction "DN1_A7") (pintype "unspecified"))
      (node (ref "USB1") (pin "B7") (pinfunction "DN2_B7") (pintype "unspecified"))
    )
    (net (code "41") (name "/USB_DP") (class "Default")
      (node (ref "U2") (pin "5") (pinfunction "D+_5") (pintype "unspecified"))
      (node (ref "USB1") (pin "A6") (pinfunction "DP1_A6") (pintype "unspecified"))
      (node (ref "USB1") (pin "B6") (pinfunction "DP2_B6") (pintype "unspecified"))
    )
    (net (code "42") (name "GND") (class "Default")
      (node (ref "C10") (pin "1") (pinfunction "1_1") (pintype "unspecified"))
      (node (ref "C11") (pin "2") (pinfunction "2_2") (pintype "unspecified"))
      (node (ref "C12") (pin "2") (pinfunction "2_2") (pintype "unspecified"))
      (node (ref "C13") (pin "1") (pinfunction "1_1") (pintype "unspecified"))
      (node (ref "C14") (pin "2") (pinfunction "2_2") (pintype "unspecified"))
      (node (ref "C16") (pin "1") (pinfunction "1_1") (pintype "unspecified"))
      (node (ref "C18") (pin "1") (pinfunction "1_1") (pintype "unspecified"))
      (node (ref "C19") (pin "2") (pinfunction "2_2") (pintype "unspecified"))
      (node (ref "C2") (pin "2") (pinfunction "2_2") (pintype "unspecified"))
      (node (ref "C20") (pin "1") (pinfunction "1_1") (pintype "unspecified"))
      (node (ref "C21") (pin "1") (pinfunction "1_1") (pintype "unspecified"))
      (node (ref "C22") (pin "1") (pinfunction "1_1") (pintype "unspecified"))
      (node (ref "C23") (pin "1") (pinfunction "1_1") (pintype "unspecified"))
      (node (ref "C3") (pin "1") (pinfunction "1_1") (pintype "unspecified"))
      (node (ref "C4") (pin "1") (pinfunction "1_1") (pintype "unspecified"))
      (node (ref "C5") (pin "1") (pinfunction "1_1") (pintype "unspecified"))
      (node (ref "C6") (pin "2") (pinfunction "2_2") (pintype "input"))
      (node (ref "C7") (pin "1") (pinfunction "1_1") (pintype "unspecified"))
      (node (ref "C8") (pin "1") (pinfunction "1_1") (pintype "unspecified"))
      (node (ref "C9") (pin "1") (pinfunction "1_1") (pintype "unspecified"))
      (node (ref "CARD1") (pin "10") (pinfunction "GND_10") (pintype "input"))
      (node (ref "CARD1") (pin "11") (pinfunction "GND_11") (pintype "input"))
      (node (ref "CARD1") (pin "12") (pinfunction "GND_12") (pintype "input"))
      (node (ref "CARD1") (pin "13") (pinfunction "GND_13") (pintype "input"))
      (node (ref "CARD1") (pin "6") (pinfunction "VSS_6") (pintype "input"))
      (node (ref "FPC1") (pin "1") (pinfunction "1_1") (pintype "unspecified"))
      (node (ref "FPC1") (pin "7") (pinfunction "7_7") (pintype "unspecified"))
      (node (ref "FPC1") (pin "8") (pinfunction "8_8") (pintype "unspecified"))
      (node (ref "FPC2") (pin "1") (pinfunction "1_1") (pintype "input"))
      (node (ref "FPC2") (pin "12") (pinfunction "12_12") (pintype "input"))
      (node (ref "FPC2") (pin "18") (pinfunction "18_18") (pintype "input"))
      (node (ref "FPC2") (pin "19") (pinfunction "19_19") (pintype "input"))
      (node (ref "FPC2") (pin "20") (pinfunction "20_20") (pintype "input"))
      (node (ref "FPC2") (pin "5") (pinfunction "5_5") (pintype "input"))
      (node (ref "FPC2") (pin "6") (pinfunction "6_6") (pintype "input"))
      (node (ref "FPC3") (pin "1") (pinfunction "1_1") (pintype "input"))
      (node (ref "FPC3") (pin "11") (pinfunction "11_11") (pintype "input"))
      (node (ref "FPC3") (pin "12") (pinfunction "12_12") (pintype "input"))
      (node (ref "LED") (pin "1") (pinfunction "K_1") (pintype "unspecified"))
      (node (ref "LED1") (pin "2") (pinfunction "GND_2") (pintype "unspecified"))
      (node (ref "PWR") (pin "1") (pinfunction "K_1") (pintype "unspecified"))
      (node (ref "Q4") (pin "2") (pinfunction "S_2") (pintype "unspecified"))
      (node (ref "Q7") (pin "2") (pinfunction "E_2") (pintype "input"))
      (node (ref "R15") (pin "2") (pinfunction "2_2") (pintype "input"))
      (node (ref "R16") (pin "1") (pinfunction "1_1") (pintype "input"))
      (node (ref "R20") (pin "1") (pinfunction "1_1") (pintype "input"))
      (node (ref "R25") (pin "1") (pinfunction "1_1") (pintype "input"))
      (node (ref "R28") (pin "1") (pinfunction "1_1") (pintype "input"))
      (node (ref "R29") (pin "1") (pinfunction "1_1") (pintype "input"))
      (node (ref "R7") (pin "2") (pinfunction "2_2") (pintype "input"))
      (node (ref "R9") (pin "1") (pinfunction "1_1") (pintype "input"))
      (node (ref "SW1") (pin "2") (pinfunction "2_2") (pintype "input"))
      (node (ref "SW2") (pin "2") (pinfunction "2_2") (pintype "input"))
      (node (ref "SW3") (pin "2") (pinfunction "2_2") (pintype "input"))
      (node (ref "SW4") (pin "2") (pinfunction "2_2") (pintype "input"))
      (node (ref "U1") (pin "1") (pinfunction "GND_1") (pintype "input"))
      (node (ref "U1") (pin "40") (pinfunction "GND_40") (pintype "input"))
      (node (ref "U1") (pin "41") (pinfunction "GND_41") (pintype "input"))
      (node (ref "U10") (pin "1") (pinfunction "1_1") (pintype "unspecified"))
      (node (ref "U2") (pin "1") (pinfunction "GND_1") (pintype "unspecified"))
      (node (ref "U3") (pin "11") (pinfunction "GND_11") (pintype "unspecified"))
      (node (ref "U3") (pin "15") (pinfunction "GND_15") (pintype "unspecified"))
      (node (ref "U3") (pin "17") (pinfunction "EP_17") (pintype "unspecified"))
      (node (ref "U3") (pin "3") (pinfunction "GND_3") (pintype "unspecified"))
      (node (ref "U4") (pin "1") (pinfunction "ADJ(GND)_1") (pintype "unspecified"))
      (node (ref "U6") (pin "1") (pinfunction "VSS_1") (pintype "unspecified"))
      (node (ref "U8") (pin "4") (pinfunction "L/R_4") (pintype "unspecified"))
      (node (ref "U8") (pin "5") (pinfunction "GND_5") (pintype "unspecified"))
      (node (ref "U8") (pin "6") (pinfunction "GND_6") (pintype "unspecified"))
      (node (ref "U8") (pin "9") (pinfunction "GND_9") (pintype "unspecified"))
      (node (ref "USB1") (pin "1") (pinfunction "EP_1") (pintype "unspecified"))
      (node (ref "USB1") (pin "2") (pinfunction "EP_2") (pintype "unspecified"))
      (node (ref "USB1") (pin "3") (pinfunction "EP_3") (pintype "unspecified"))
      (node (ref "USB1") (pin "4") (pinfunction "EP_4") (pintype "unspecified"))
      (node (ref "USB1") (pin "A1") (pinfunction "GND_A1") (pintype "unspecified"))
      (node (ref "USB1") (pin "A12") (pinfunction "GND_A12") (pintype "unspecified"))
      (node (ref "USB1") (pin "B1") (pinfunction "GND_B1") (pintype "unspecified"))
      (node (ref "USB1") (pin "B12") (pinfunction "GND_B12") (pintype "unspecified"))
      (node (ref "USB2") (pin "1") (pinfunction "EP_1") (pintype "unspecified"))
      (node (ref "USB2") (pin "2") (pinfunction "EP_2") (pintype "unspecified"))
      (node (ref "USB2") (pin "3") (pinfunction "EP_3") (pintype "unspecified"))
      (node (ref "USB2") (pin "4") (pinfunction "EP_4") (pintype "unspecified"))
      (node (ref "USB2") (pin "A1") (pinfunction "GND_A1") (pintype "unspecified"))
      (node (ref "USB2") (pin "A12") (pinfunction "GND_A12") (pintype "unspecified"))
      (node (ref "USB2") (pin "B1") (pinfunction "GND_B1") (pintype "unspecified"))
      (node (ref "USB2") (pin "B12") (pinfunction "GND_B12") (pintype "unspecified"))
    )
    (net (code "43") (name "Net-(LED-A)") (class "Default")
      (node (ref "LED") (pin "2") (pinfunction "A_2") (pintype "unspecified"))
      (node (ref "R1") (pin "1") (pinfunction "1_1") (pintype "input"))
    )
    (net (code "44") (name "Net-(PWR-A)") (class "Default")
      (node (ref "PWR") (pin "2") (pinfunction "A_2") (pintype "unspecified"))
      (node (ref "R3") (pin "1") (pinfunction "1_1") (pintype "input"))
    )
    (net (code "45") (name "Net-(Q1-B)") (class "Default")
      (node (ref "Q1") (pin "1") (pinfunction "B_1") (pintype "input"))
      (node (ref "R10") (pin "1") (pinfunction "1_1") (pintype "input"))
    )
    (net (code "46") (name "Net-(Q4-D)") (class "Default")
      (node (ref "Q4") (pin "3") (pinfunction "D_3") (pintype "unspecified"))
      (node (ref "R23") (pin "1") (pinfunction "1_1") (pintype "input"))
    )
    (net (code "47") (name "Net-(Q4-G)") (class "Default")
      (node (ref "Q4") (pin "1") (pinfunction "G_1") (pintype "unspecified"))
      (node (ref "R24") (pin "2") (pinfunction "2_2") (pintype "input"))
      (node (ref "R25") (pin "2") (pinfunction "2_2") (pintype "input"))
    )
    (net (code "48") (name "Net-(Q6-B)") (class "Default")
      (node (ref "Q6") (pin "1") (pinfunction "B_1") (pintype "input"))
      (node (ref "R11") (pin "1") (pinfunction "1_1") (pintype "input"))
    )
    (net (code "49") (name "Net-(Q7-C)") (class "Default")
      (node (ref "Q7") (pin "3") (pinfunction "C_3") (pintype "input"))
      (node (ref "R19") (pin "1") (pinfunction "1_1") (pintype "input"))
    )
    (net (code "50") (name "Net-(R13-Pad2)") (class "Default")
      (node (ref "R13") (pin "2") (pinfunction "2_2") (pintype "input"))
      (node (ref "R14") (pin "1") (pinfunction "1_1") (pintype "input"))
    )
    (net (code "51") (name "Net-(TX-A)") (class "Default")
      (node (ref "R2") (pin "1") (pinfunction "1_1") (pintype "input"))
      (node (ref "TX") (pin "2") (pinfunction "A_2") (pintype "unspecified"))
    )
    (net (code "52") (name "Net-(U1-IO3)") (class "Default")
      (node (ref "R13") (pin "1") (pinfunction "1_1") (pintype "input"))
      (node (ref "U1") (pin "15") (pinfunction "IO3_15") (pintype "input"))
    )
    (net (code "53") (name "Net-(U1-IO17)") (class "Default")
      (node (ref "U1") (pin "10") (pinfunction "IO17_10") (pintype "input"))
      (node (ref "U10") (pin "2") (pinfunction "2_2") (pintype "unspecified"))
    )
    (net (code "54") (name "Net-(U1-IO18)") (class "Default")
      (node (ref "U1") (pin "11") (pinfunction "IO18_11") (pintype "input"))
      (node (ref "U10") (pin "3") (pinfunction "3_3") (pintype "unspecified"))
    )
    (net (code "55") (name "Net-(U2-RXD)") (class "Default")
      (node (ref "R27") (pin "1") (pinfunction "1_1") (pintype "input"))
      (node (ref "U2") (pin "3") (pinfunction "RXD_3") (pintype "unspecified"))
    )
    (net (code "56") (name "Net-(U2-TXD)") (class "Default")
      (node (ref "R26") (pin "1") (pinfunction "1_1") (pintype "input"))
      (node (ref "U2") (pin "2") (pinfunction "TXD_2") (pintype "unspecified"))
    )
    (net (code "57") (name "Net-(U2-V3)") (class "Default")
      (node (ref "C21") (pin "2") (pinfunction "2_2") (pintype "unspecified"))
      (node (ref "U2") (pin "4") (pinfunction "V3_4") (pintype "unspecified"))
    )
    (net (code "58") (name "Net-(U3-GAIN_SLOT)") (class "Default")
      (node (ref "R7") (pin "1") (pinfunction "1_1") (pintype "input"))
      (node (ref "U3") (pin "2") (pinfunction "GAIN_SLOT_2") (pintype "unspecified"))
    )
    (net (code "59") (name "Net-(U3-OUTN)") (class "Default")
      (node (ref "U3") (pin "10") (pinfunction "OUTN_10") (pintype "unspecified"))
      (node (ref "U9") (pin "1") (pinfunction "1_1") (pintype "unspecified"))
    )
    (net (code "60") (name "Net-(U3-OUTP)") (class "Default")
      (node (ref "U3") (pin "9") (pinfunction "OUTP_9") (pintype "unspecified"))
      (node (ref "U9") (pin "2") (pinfunction "2_2") (pintype "unspecified"))
    )
    (net (code "61") (name "Net-(U3-SD_MODE#)") (class "Default")
      (node (ref "R8") (pin "1") (pinfunction "1_1") (pintype "input"))
      (node (ref "U3") (pin "4") (pinfunction "SD_MODE#_4") (pintype "unspecified"))
    )
    (net (code "62") (name "VCC") (class "Default")
      (node (ref "C12") (pin "1") (pinfunction "1_1") (pintype "unspecified"))
      (node (ref "C16") (pin "2") (pinfunction "2_2") (pintype "unspecified"))
      (node (ref "C18") (pin "2") (pinfunction "2_2") (pintype "unspecified"))
      (node (ref "C22") (pin "2") (pinfunction "2_2") (pintype "unspecified"))
      (node (ref "C23") (pin "2") (pinfunction "2_2") (pintype "unspecified"))
      (node (ref "C6") (pin "1") (pinfunction "1_1") (pintype "input"))
      (node (ref "C7") (pin "2") (pinfunction "2_2") (pintype "unspecified"))
      (node (ref "C8") (pin "2") (pinfunction "2_2") (pintype "unspecified"))
      (node (ref "C9") (pin "2") (pinfunction "2_2") (pintype "unspecified"))
      (node (ref "CARD1") (pin "4") (pinfunction "VDD_4") (pintype "input"))
      (node (ref "FPC1") (pin "6") (pinfunction "6_6") (pintype "unspecified"))
      (node (ref "FPC2") (pin "17") (pinfunction "17_17") (pintype "input"))
      (node (ref "FPC2") (pin "3") (pinfunction "3_3") (pintype "input"))
      (node (ref "FPC2") (pin "4") (pinfunction "4_4") (pintype "input"))
      (node (ref "FPC3") (pin "7") (pinfunction "7_7") (pintype "input"))
      (node (ref "R12") (pin "2") (pinfunction "2_2") (pintype "input"))
      (node (ref "R14") (pin "2") (pinfunction "2_2") (pintype "input"))
      (node (ref "R2") (pin "2") (pinfunction "2_2") (pintype "input"))
      (node (ref "R21") (pin "1") (pinfunction "1_1") (pintype "input"))
      (node (ref "R22") (pin "1") (pinfunction "1_1") (pintype "input"))
      (node (ref "R3") (pin "2") (pinfunction "2_2") (pintype "input"))
      (node (ref "R30") (pin "2") (pinfunction "2_2") (pintype "input"))
      (node (ref "R31") (pin "2") (pinfunction "2_2") (pintype "input"))
      (node (ref "R32") (pin "2") (pinfunction "2_2") (pintype "input"))
      (node (ref "R34") (pin "2") (pinfunction "2_2") (pintype "input"))
      (node (ref "R4") (pin "2") (pinfunction "2_2") (pintype "input"))
      (node (ref "R5") (pin "2") (pinfunction "2_2") (pintype "input"))
      (node (ref "R6") (pin "2") (pinfunction "2_2") (pintype "input"))
      (node (ref "R8") (pin "2") (pinfunction "2_2") (pintype "input"))
      (node (ref "U1") (pin "2") (pinfunction "3V3_2") (pintype "input"))
      (node (ref "U3") (pin "7") (pinfunction "VDD_7") (pintype "unspecified"))
      (node (ref "U3") (pin "8") (pinfunction "VDD_8") (pintype "unspecified"))
      (node (ref "U4") (pin "2") (pinfunction "VOUT(TAB)_2") (pintype "unspecified"))
      (node (ref "U4") (pin "4") (pinfunction "TAB_4") (pintype "unspecified"))
      (node (ref "U6") (pin "3") (pinfunction "VIN_3") (pintype "unspecified"))
      (node (ref "U8") (pin "7") (pinfunction "VDD_7") (pintype "unspecified"))
      (node (ref "U8") (pin "8") (pinfunction "CHIPEN_8") (pintype "unspecified"))
    )
    (net (code "63") (name "unconnected-(CARD1-CD-Pad9)") (class "Default")
      (node (ref "CARD1") (pin "9") (pinfunction "CD_9") (pintype "input+no_connect"))
    )
    (net (code "64") (name "unconnected-(CARD1-CDDAT3(CS)-Pad2)") (class "Default")
      (node (ref "CARD1") (pin "2") (pinfunction "CDDAT3(CS)_2") (pintype "bidirectional+no_connect"))
    )
    (net (code "65") (name "unconnected-(CARD1-DAT1(RSV)-Pad8)") (class "Default")
      (node (ref "CARD1") (pin "8") (pinfunction "DAT1(RSV)_8") (pintype "bidirectional+no_connect"))
    )
    (net (code "66") (name "unconnected-(CARD1-DAT2(RSV)-Pad1)") (class "Default")
      (node (ref "CARD1") (pin "1") (pinfunction "DAT2(RSV)_1") (pintype "bidirectional+no_connect"))
    )
    (net (code "67") (name "unconnected-(FPC3-Pad9)") (class "Default")
      (node (ref "FPC3") (pin "9") (pinfunction "9_9") (pintype "input+no_connect"))
    )
    (net (code "68") (name "unconnected-(LED1-DO-Pad1)") (class "Default")
      (node (ref "LED1") (pin "1") (pinfunction "DO_1") (pintype "unspecified+no_connect"))
    )
    (net (code "69") (name "unconnected-(SCREW1-Pad1)") (class "Default")
      (node (ref "SCREW1") (pin "1") (pinfunction "1_1") (pintype "input"))
    )
    (net (code "70") (name "unconnected-(SCREW2-Pad1)") (class "Default")
      (node (ref "SCREW2") (pin "1") (pinfunction "1_1") (pintype "input"))
    )
    (net (code "71") (name "unconnected-(SCREW3-Pad1)") (class "Default")
      (node (ref "SCREW3") (pin "1") (pinfunction "1_1") (pintype "input"))
    )
    (net (code "72") (name "unconnected-(SCREW4-Pad1)") (class "Default")
      (node (ref "SCREW4") (pin "1") (pinfunction "1_1") (pintype "input"))
    )
    (net (code "73") (name "unconnected-(U1-IO8-Pad12)") (class "Default")
      (node (ref "U1") (pin "12") (pinfunction "IO8_12") (pintype "input+no_connect"))
    )
    (net (code "74") (name "unconnected-(U1-IO35-Pad28)") (class "Default")
      (node (ref "U1") (pin "28") (pinfunction "IO35_28") (pintype "input+no_connect"))
    )
    (net (code "75") (name "unconnected-(U1-IO36-Pad29)") (class "Default")
      (node (ref "U1") (pin "29") (pinfunction "IO36_29") (pintype "input+no_connect"))
    )
    (net (code "76") (name "unconnected-(U1-IO37-Pad30)") (class "Default")
      (node (ref "U1") (pin "30") (pinfunction "IO37_30") (pintype "input+no_connect"))
    )
    (net (code "77") (name "unconnected-(U1-IO46-Pad16)") (class "Default")
      (node (ref "U1") (pin "16") (pinfunction "IO46_16") (pintype "input"))
    )
    (net (code "78") (name "unconnected-(U2-CTS#-Pad9)") (class "Default")
      (node (ref "U2") (pin "9") (pinfunction "CTS#_9") (pintype "unspecified+no_connect"))
    )
    (net (code "79") (name "unconnected-(U2-DCD#-Pad12)") (class "Default")
      (node (ref "U2") (pin "12") (pinfunction "DCD#_12") (pintype "unspecified+no_connect"))
    )
    (net (code "80") (name "unconnected-(U2-DSR#-Pad10)") (class "Default")
      (node (ref "U2") (pin "10") (pinfunction "DSR#_10") (pintype "unspecified+no_connect"))
    )
    (net (code "81") (name "unconnected-(U2-NC.-Pad7)") (class "Default")
      (node (ref "U2") (pin "7") (pinfunction "NC._7") (pintype "unspecified+no_connect"))
    )
    (net (code "82") (name "unconnected-(U2-OUT#-Pad8)") (class "Default")
      (node (ref "U2") (pin "8") (pinfunction "OUT#_8") (pintype "unspecified+no_connect"))
    )
    (net (code "83") (name "unconnected-(U2-R232-Pad15)") (class "Default")
      (node (ref "U2") (pin "15") (pinfunction "R232_15") (pintype "unspecified+no_connect"))
    )
    (net (code "84") (name "unconnected-(U2-RI#-Pad11)") (class "Default")
      (node (ref "U2") (pin "11") (pinfunction "RI#_11") (pintype "unspecified+no_connect"))
    )
    (net (code "85") (name "unconnected-(U3-N.C.-Pad5)") (class "Default")
      (node (ref "U3") (pin "5") (pinfunction "N.C._5") (pintype "unspecified+no_connect"))
    )
    (net (code "86") (name "unconnected-(U3-N.C.-Pad6)") (class "Default")
      (node (ref "U3") (pin "6") (pinfunction "N.C._6") (pintype "unspecified+no_connect"))
    )
    (net (code "87") (name "unconnected-(U3-N.C.-Pad12)") (class "Default")
      (node (ref "U3") (pin "12") (pinfunction "N.C._12") (pintype "unspecified+no_connect"))
    )
    (net (code "88") (name "unconnected-(U3-N.C.-Pad13)") (class "Default")
      (node (ref "U3") (pin "13") (pinfunction "N.C._13") (pintype "unspecified+no_connect"))
    )
    (net (code "89") (name "unconnected-(USB1-SUB1-PadA8)") (class "Default")
      (node (ref "USB1") (pin "A8") (pinfunction "SUB1_A8") (pintype "unspecified+no_connect"))
    )
    (net (code "90") (name "unconnected-(USB1-SUB2-PadB8)") (class "Default")
      (node (ref "USB1") (pin "B8") (pinfunction "SUB2_B8") (pintype "unspecified+no_connect"))
    )
    (net (code "91") (name "unconnected-(USB2-SUB1-PadA8)") (class "Default")
      (node (ref "USB2") (pin "A8") (pinfunction "SUB1_A8") (pintype "unspecified"))
    )
    (net (code "92") (name "unconnected-(USB2-SUB2-PadB8)") (class "Default")
      (node (ref "USB2") (pin "B8") (pinfunction "SUB2_B8") (pintype "unspecified"))
    )
  )
)
